# Vayu.net
KiCad netlist of a schematic drawn in EAGLE
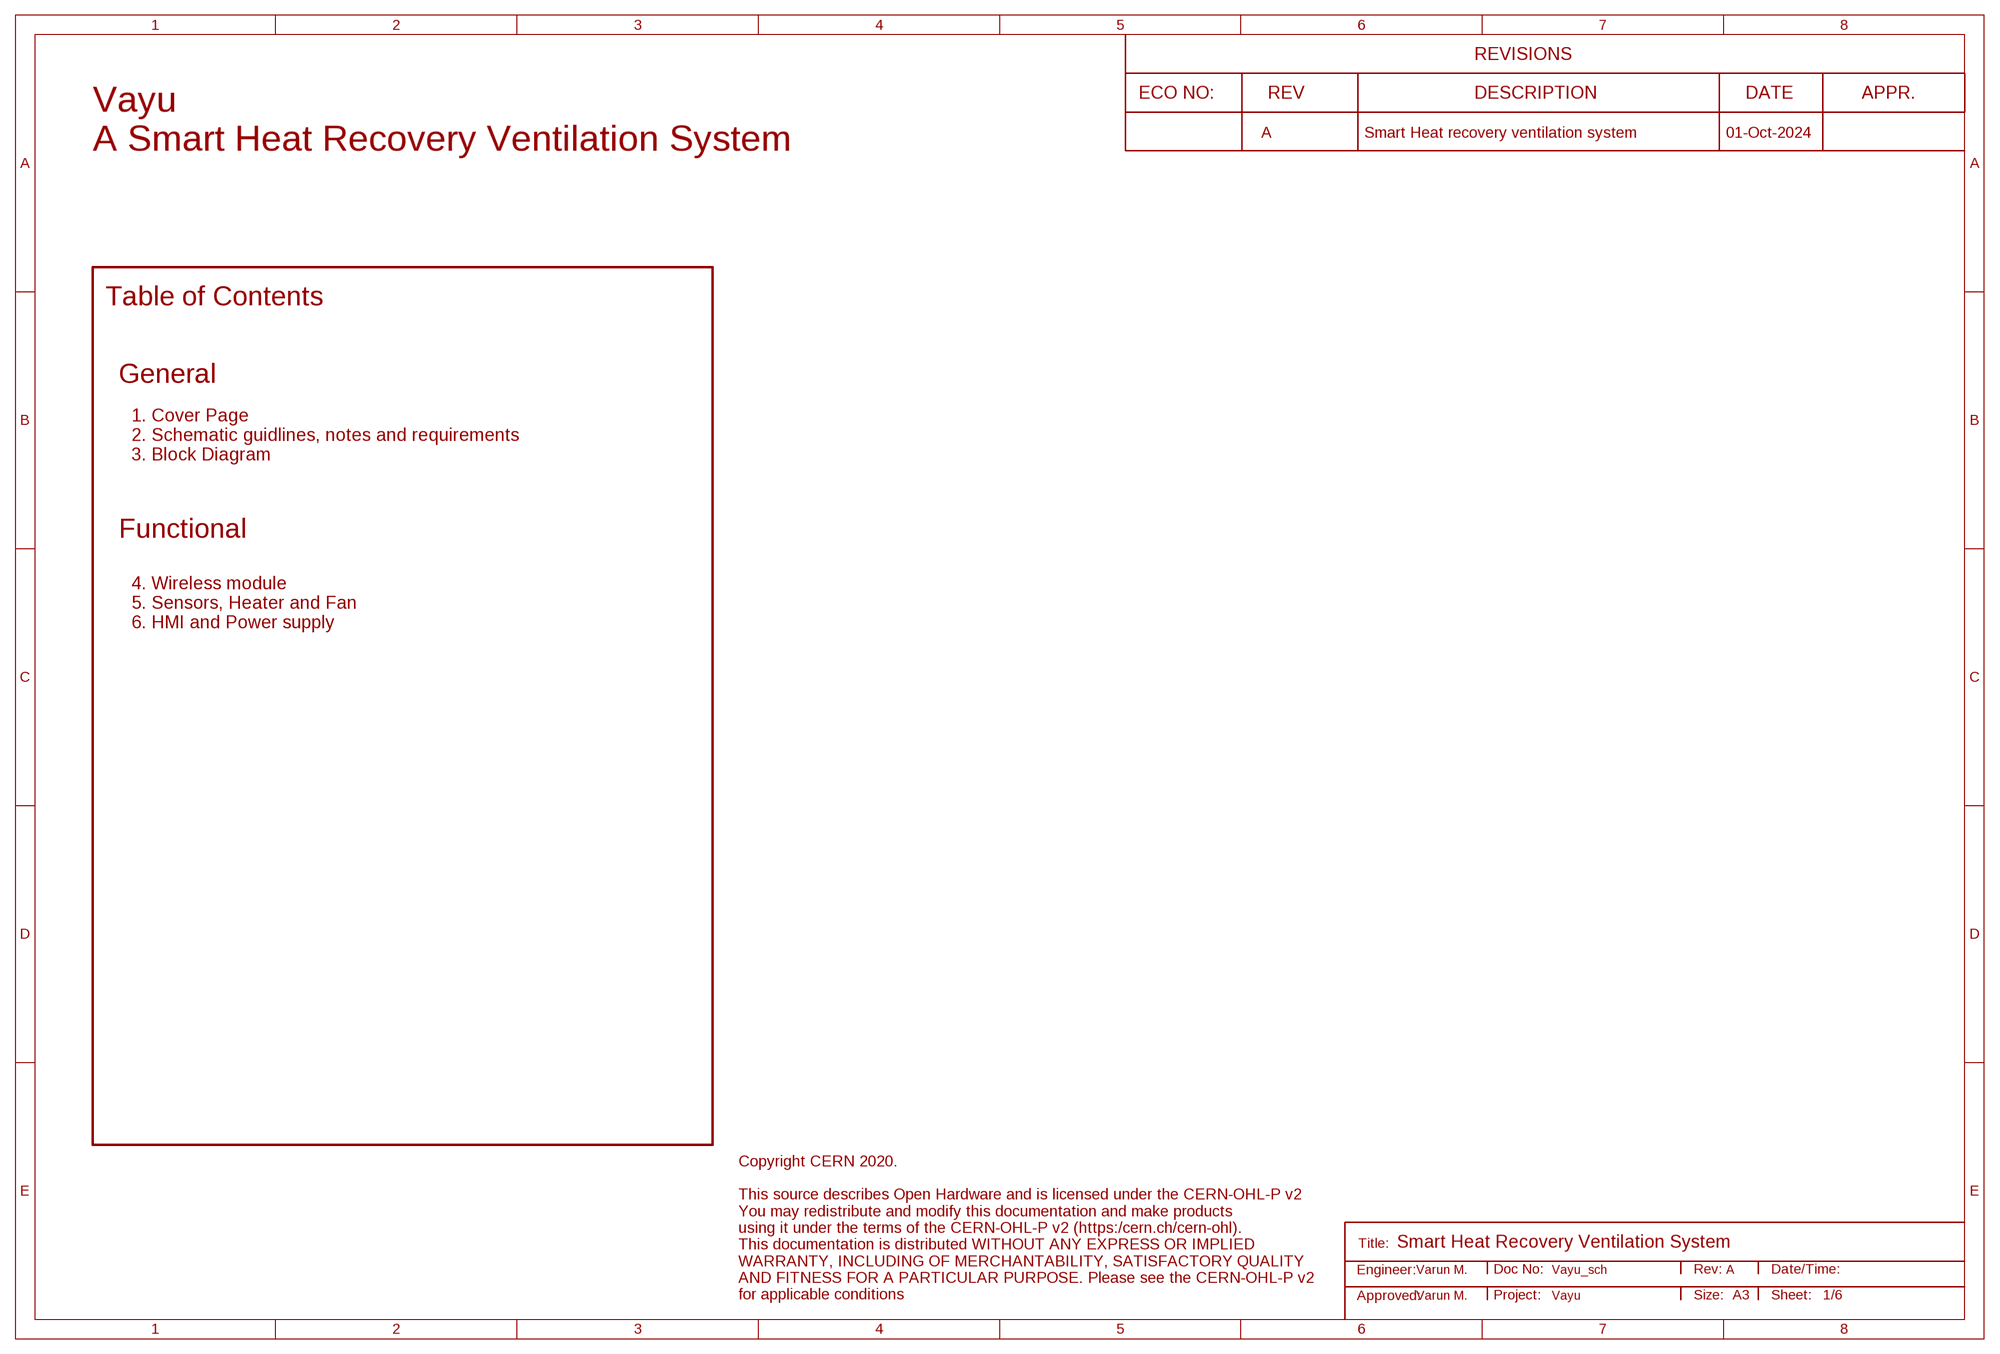
[diagram p0: schematic, sheet 1]
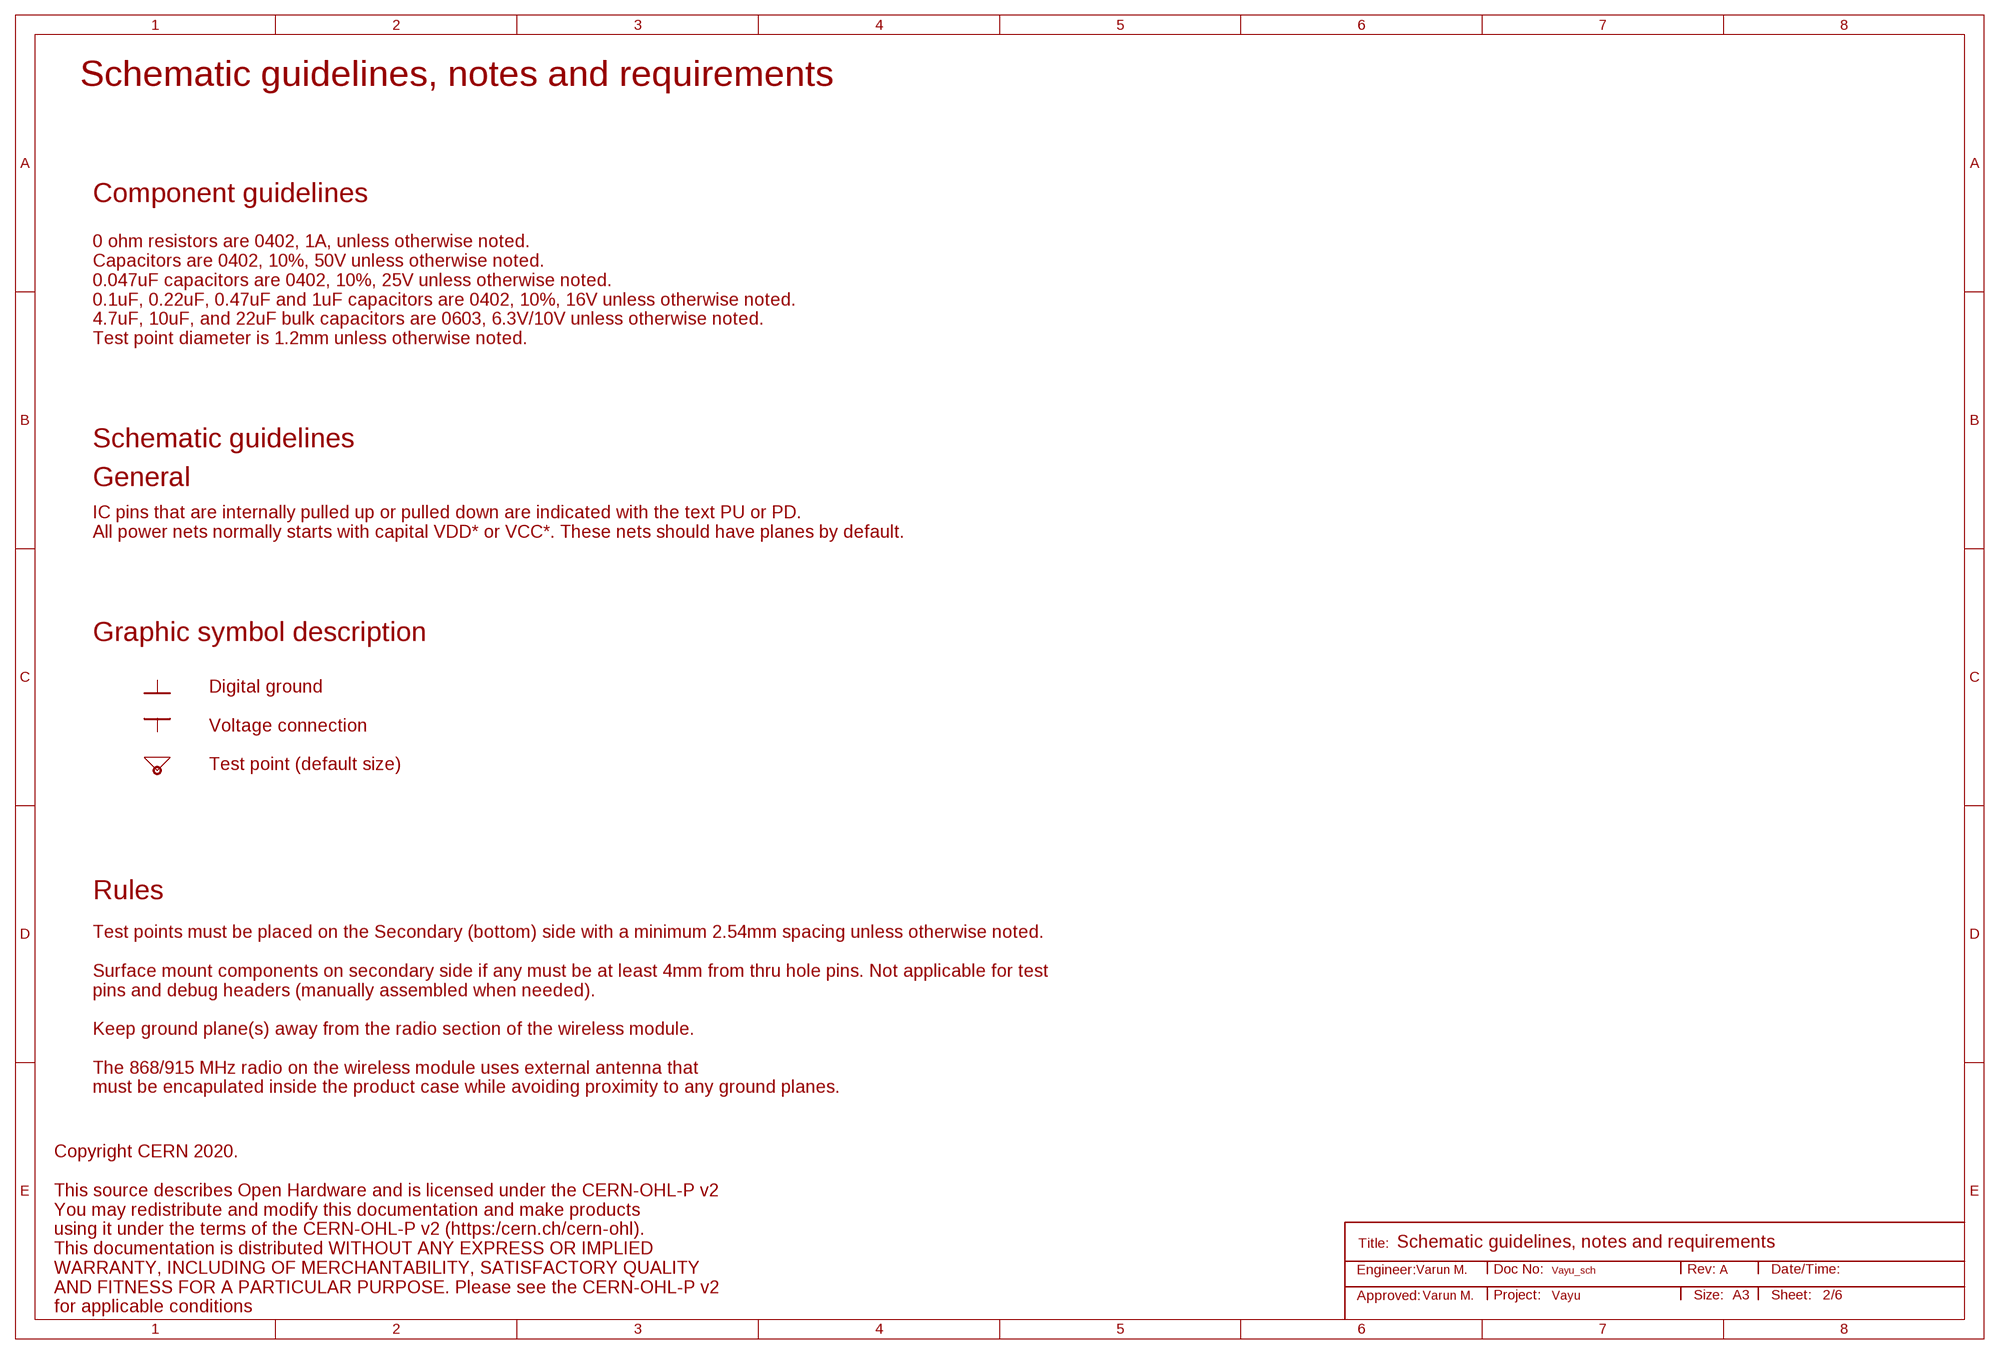
[diagram p1: schematic, sheet 2]
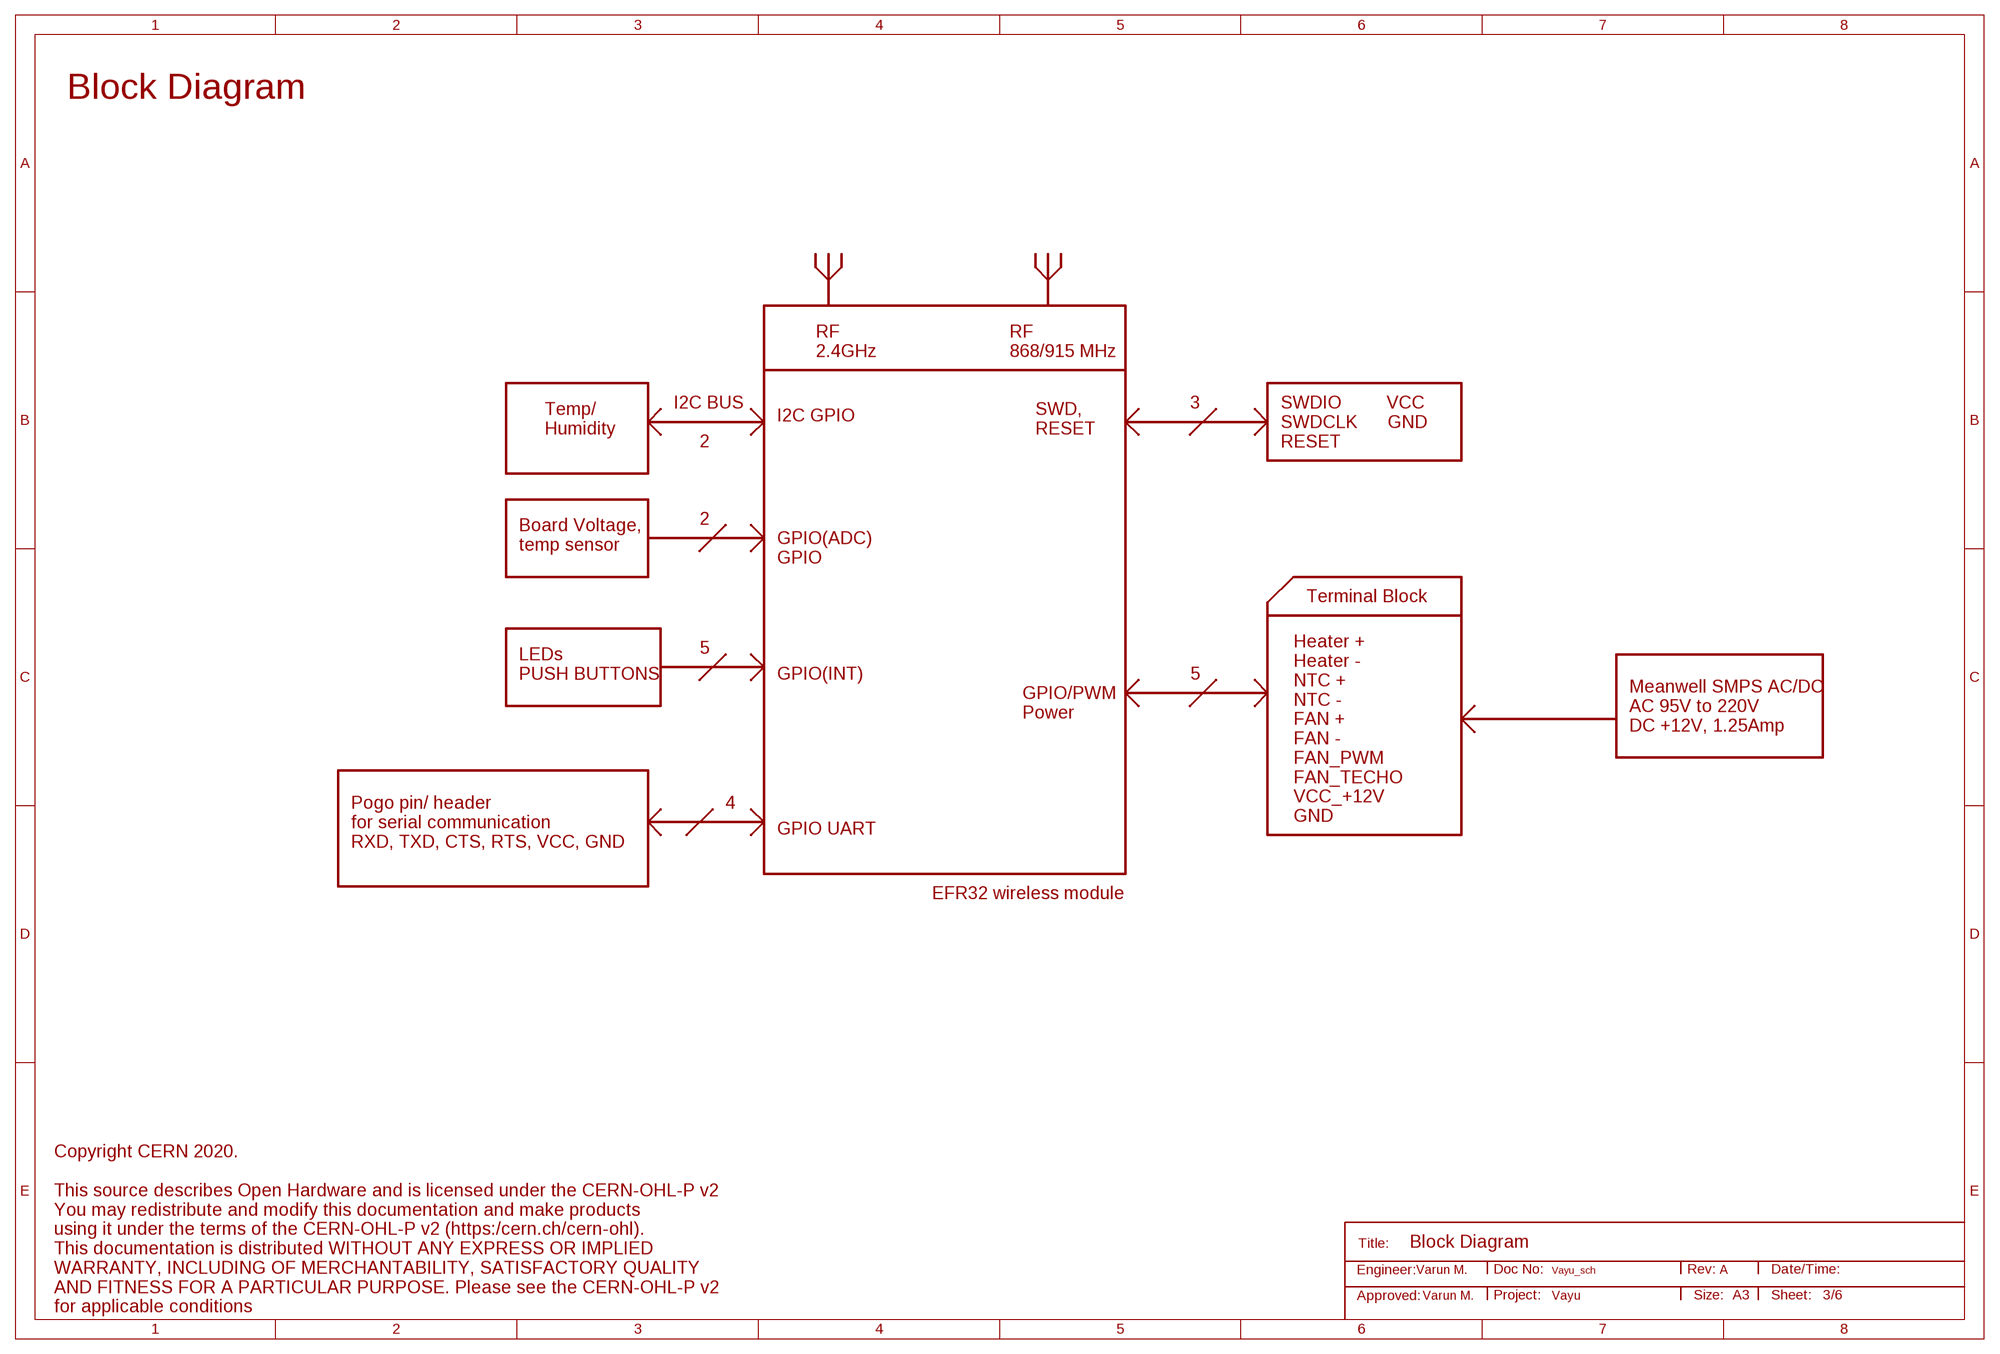
[diagram p2: schematic, sheet 3]
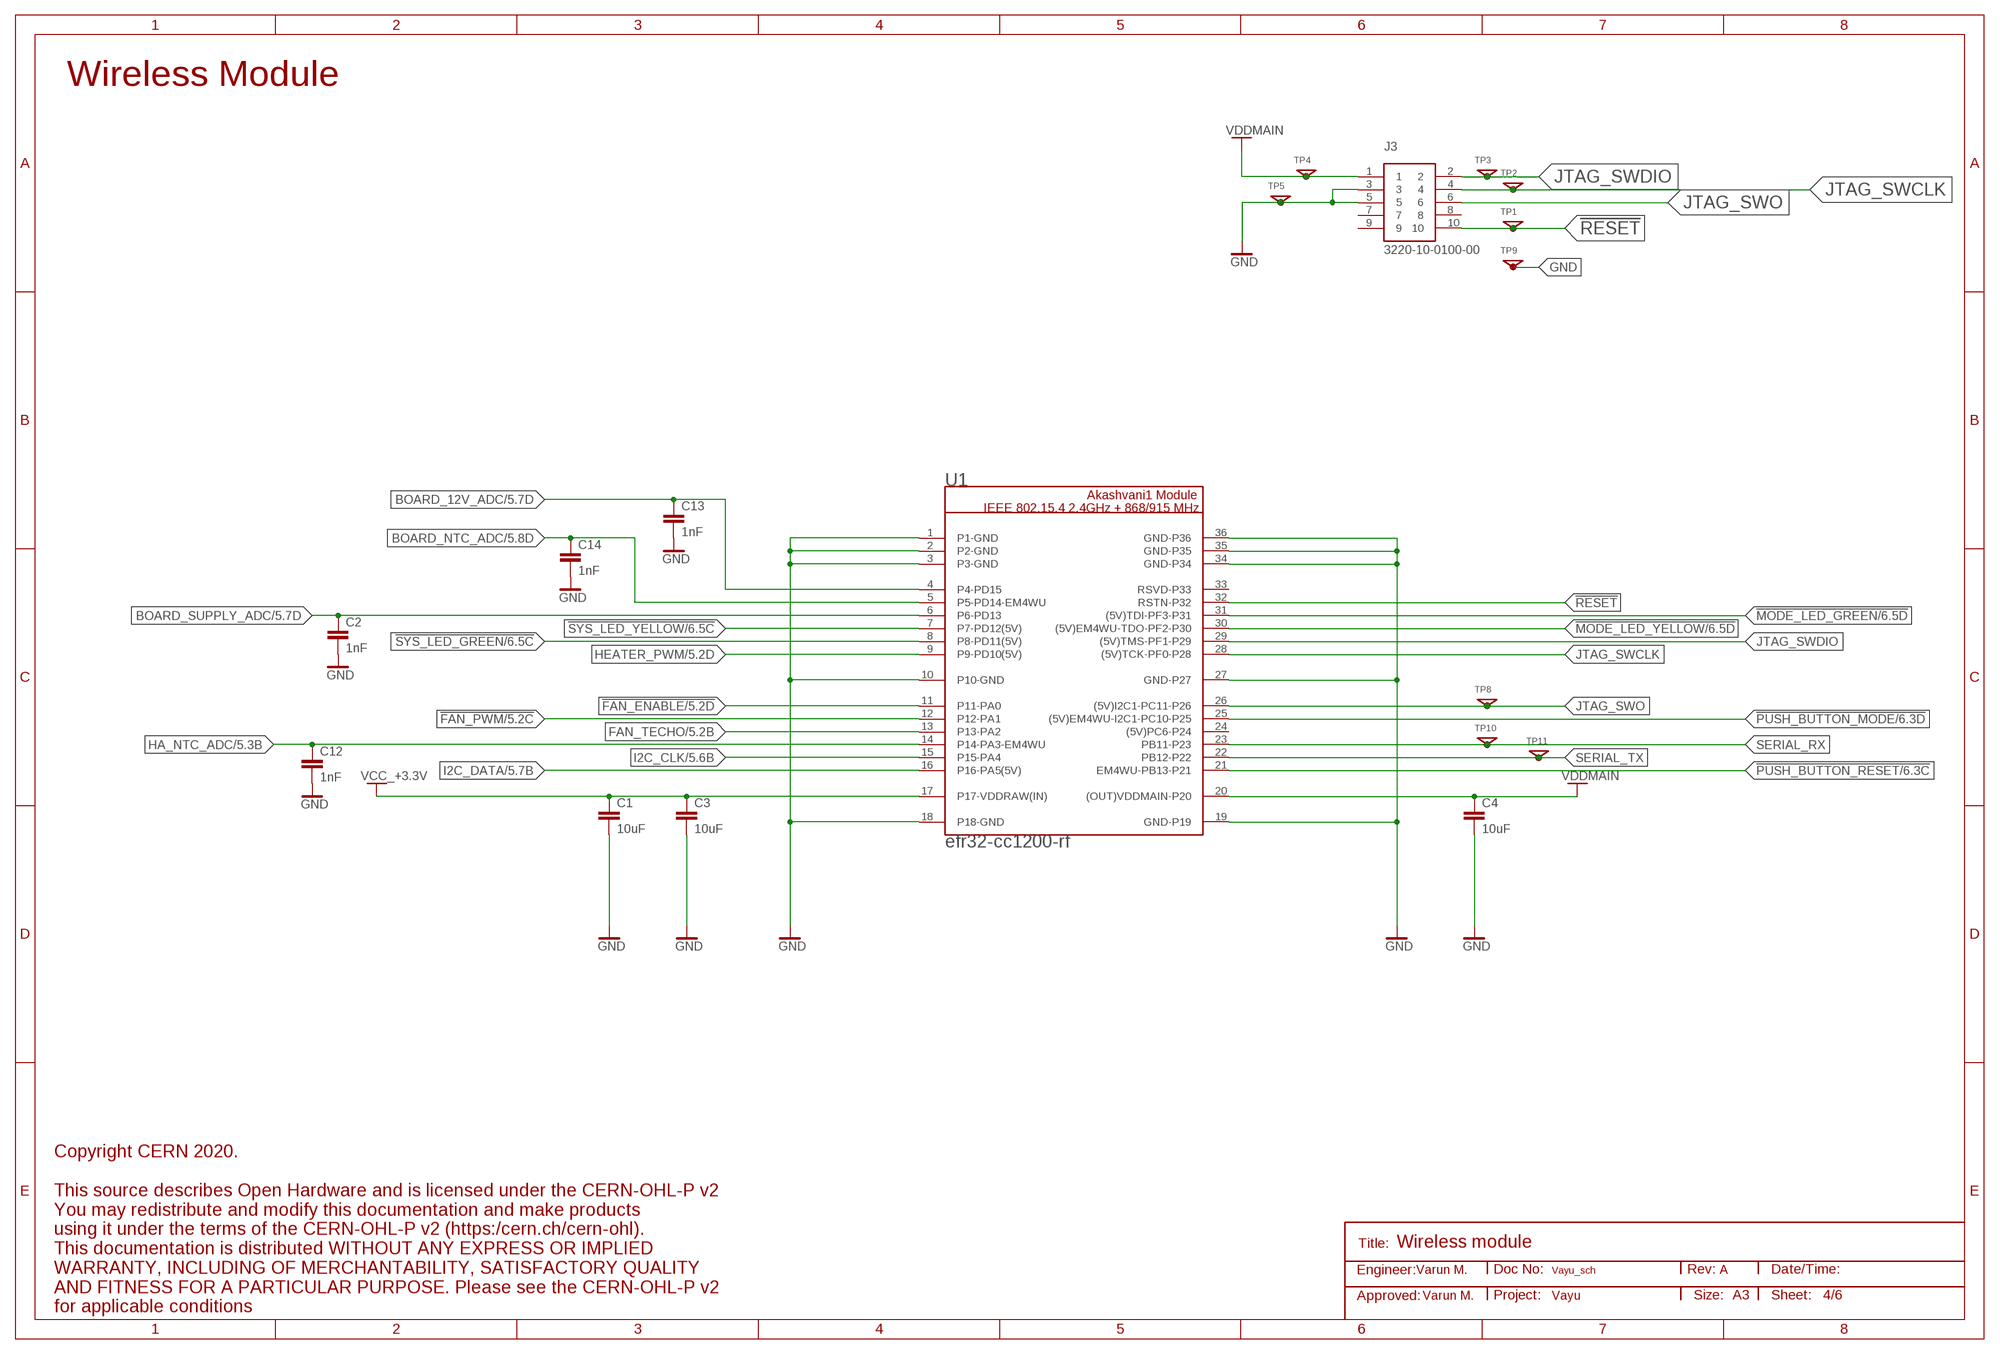
[diagram p3: schematic, sheet 4]
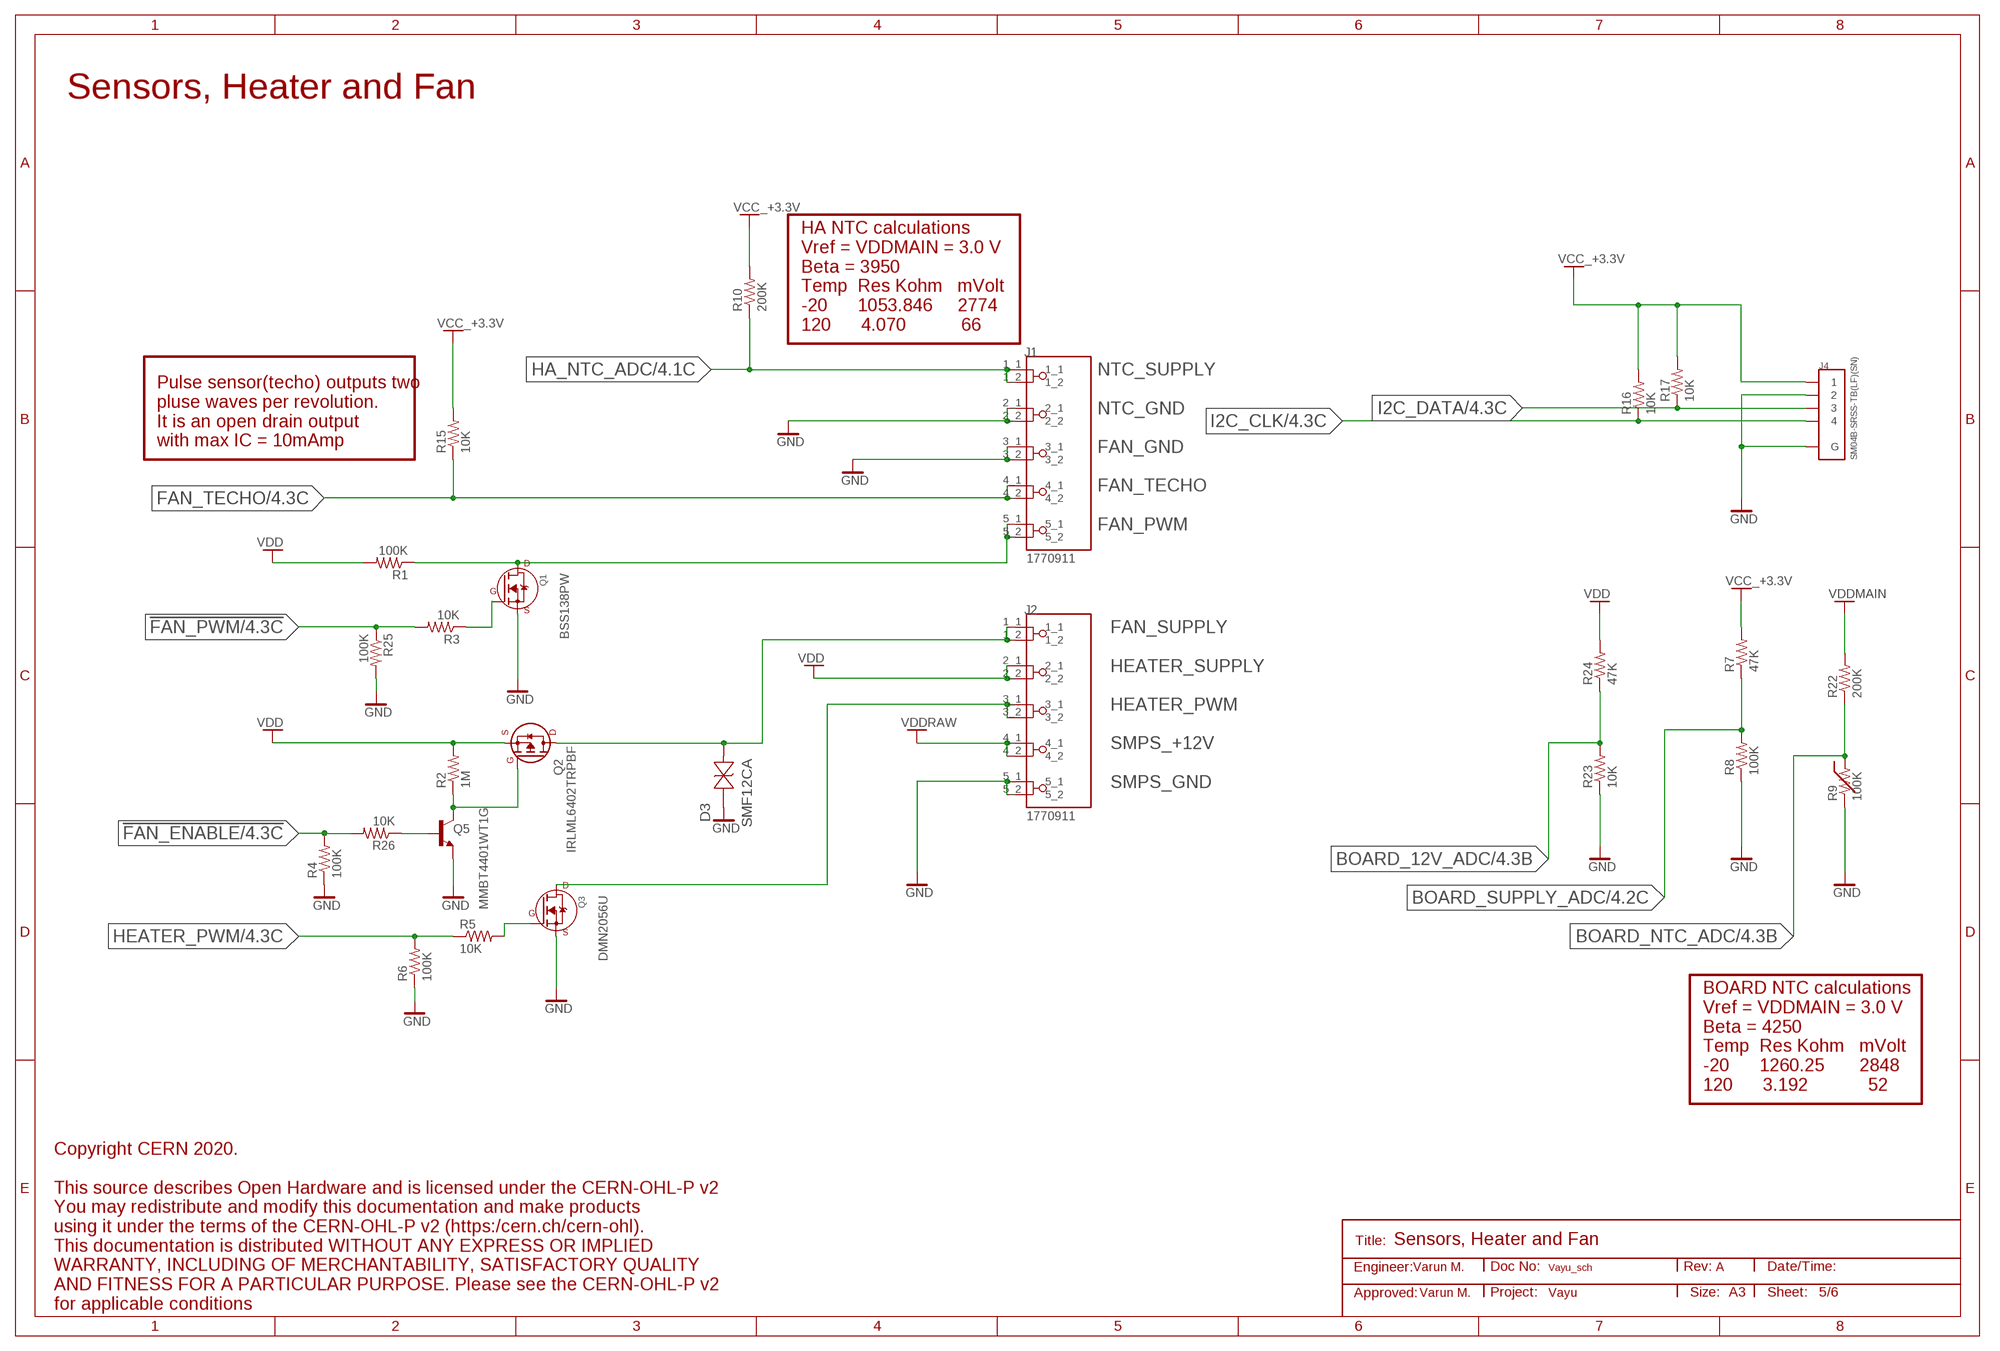
[diagram p4: schematic, sheet 5]
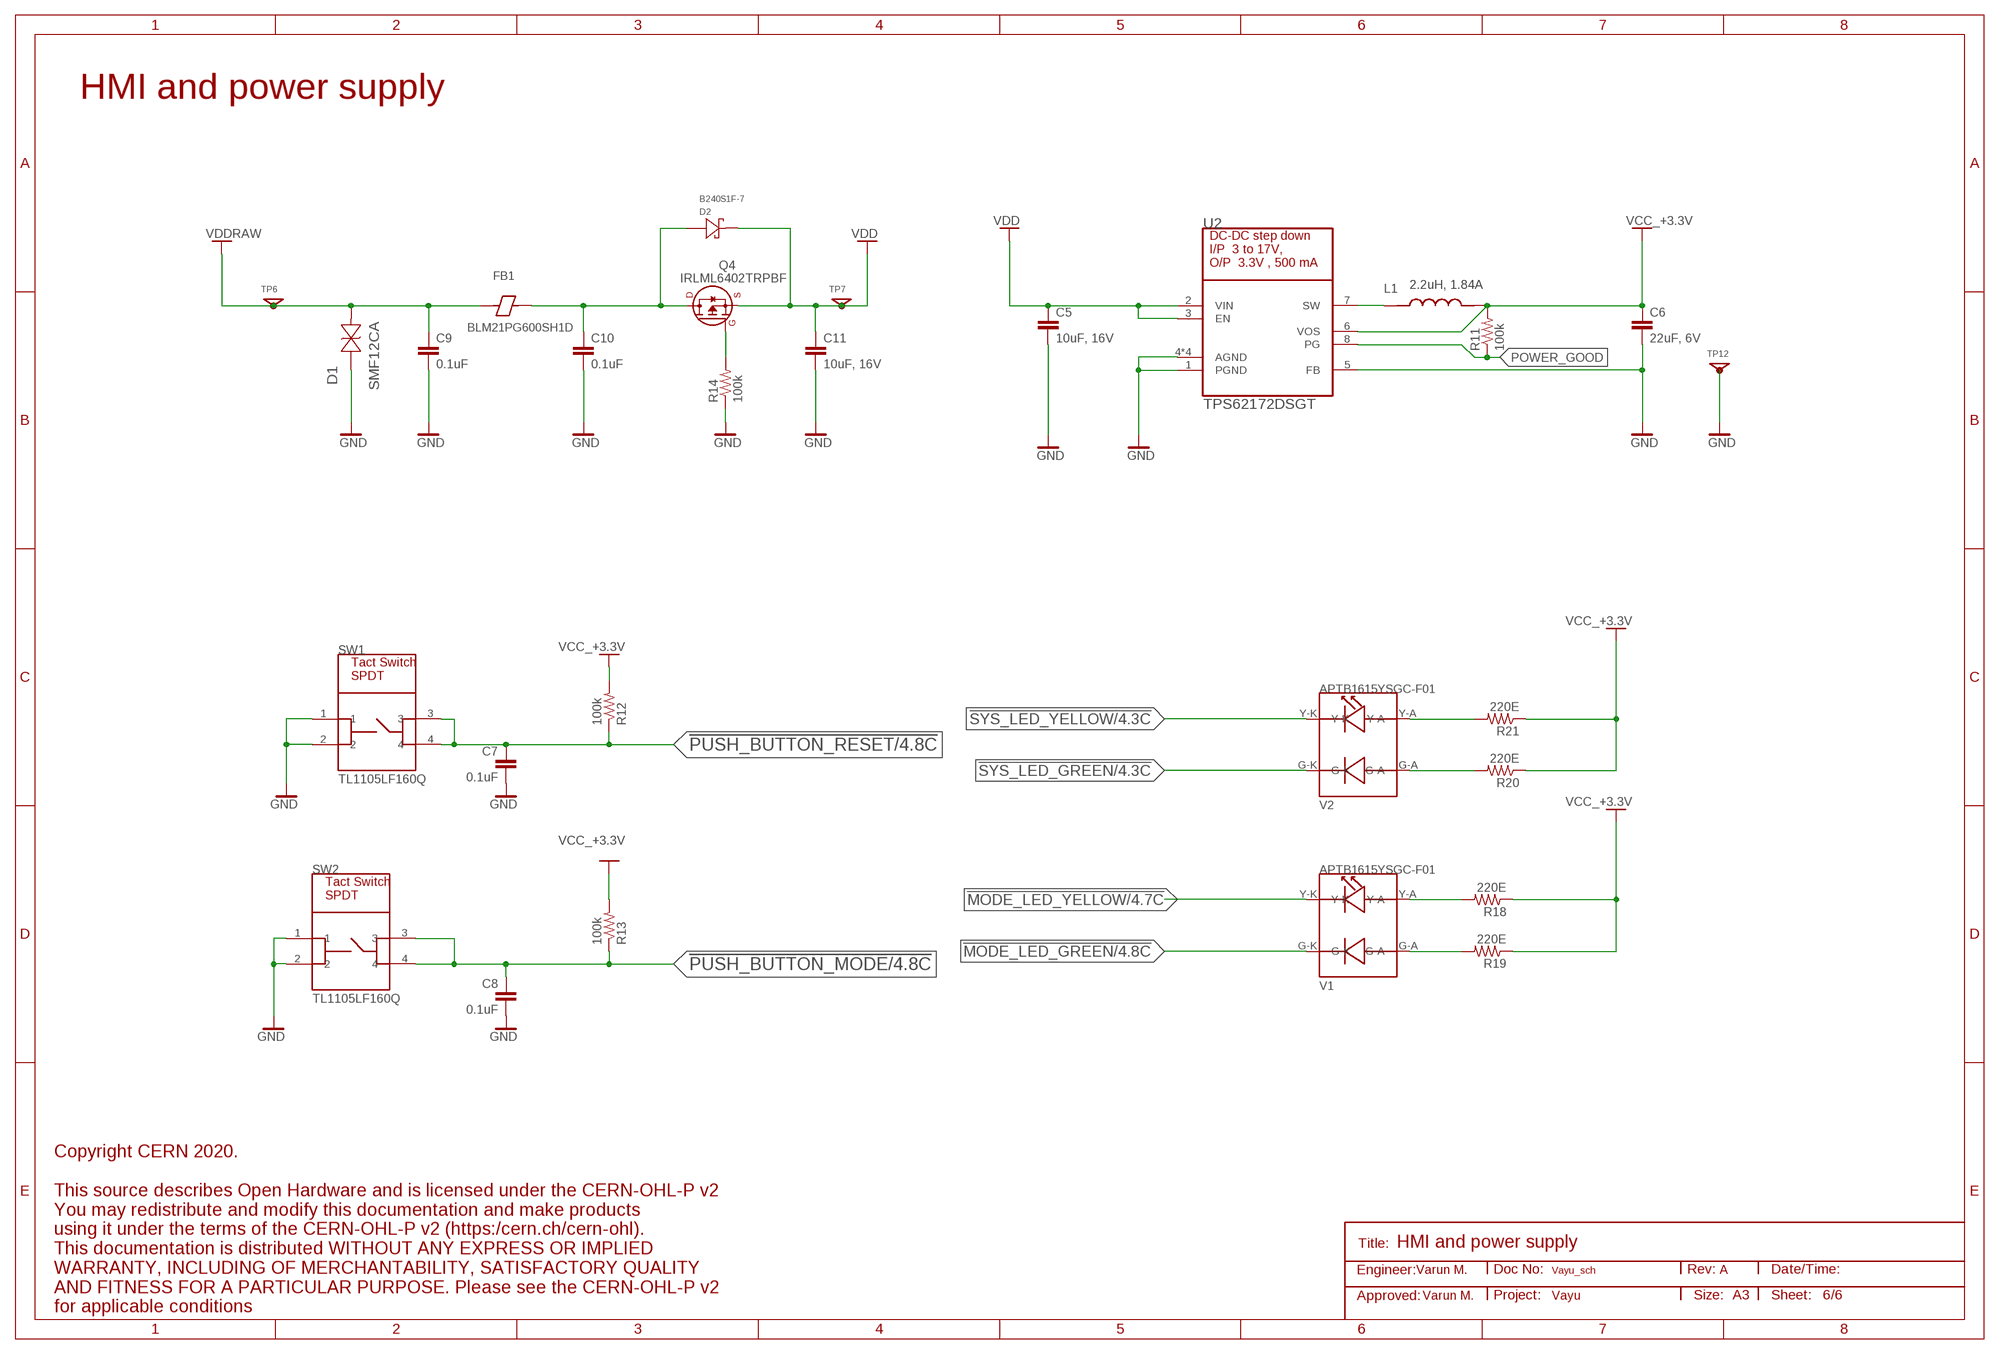
[diagram p5: schematic, sheet 6]

(export (version "E")
  (design (tool "Eeschema 10.0.6"))
  (components
    (comp (ref "D3")
      (value "SMF12CA")
      (footprint "eagle-import:SOD-123F-BI")
      (libsource (lib "eagle-import") (part "SMF12CA"))
    )
    (comp (ref "J1")
      (value "1770911")
      (footprint "eagle-import:PHOENIX_1770911")
      (fields (field (name "MANUFACTURER") "PHOENIX"))
      (libsource (lib "eagle-import") (part "1770911"))
    )
    (comp (ref "J2")
      (value "1770911")
      (footprint "eagle-import:PHOENIX_1770911")
      (fields (field (name "MANUFACTURER") "PHOENIX"))
      (libsource (lib "eagle-import") (part "1770911"))
    )
    (comp (ref "J4")
      (value "SM04B-SRSS-TB(LF)(SN)")
      (footprint "eagle-import:JST_SM04B-SRSS-TB(LF)(SN)")
      (fields (field (name "DIGI-KEY_PART_NUMBER") "455-1804-1-ND") (field (name "MF") "JST Sales"))
      (libsource (lib "eagle-import") (part "SM04B-SRSS-TB(LF)(SN)"))
    )
    (comp (ref "Q1")
      (value "BSS138PW")
      (footprint "eagle-import:SC-70_SOT323")
      (libsource (lib "eagle-import") (part "BSS138PW"))
    )
    (comp (ref "Q2")
      (value "IRLML6402TRPBF")
      (footprint "eagle-import:SOT23-3")
      (libsource (lib "eagle-import") (part "IRLML6402TRPBF"))
    )
    (comp (ref "Q3")
      (value "DMN2056U")
      (footprint "eagle-import:SOT23-3")
      (libsource (lib "eagle-import") (part "DMN2056U"))
    )
    (comp (ref "Q5")
      (value "MMBT4401WT1G")
      (footprint "eagle-import:SOT323-BEC")
      (libsource (lib "eagle-import") (part "MMBT4401WT1G"))
    )
    (comp (ref "R1")
      (value "100K")
      (footprint "eagle-import:R0402")
      (libsource (lib "eagle-import") (part "R-US_R0402"))
    )
    (comp (ref "R2")
      (value "1M")
      (footprint "eagle-import:R0402")
      (libsource (lib "eagle-import") (part "R-US_R0402"))
    )
    (comp (ref "R3")
      (value "10K")
      (footprint "eagle-import:R0402")
      (libsource (lib "eagle-import") (part "R-US_R0402"))
    )
    (comp (ref "R4")
      (value "100K")
      (footprint "eagle-import:R0402")
      (libsource (lib "eagle-import") (part "R-US_R0402"))
    )
    (comp (ref "R5")
      (value "10K")
      (footprint "eagle-import:R0402")
      (libsource (lib "eagle-import") (part "R-US_R0402"))
    )
    (comp (ref "R6")
      (value "100K")
      (footprint "eagle-import:R0402")
      (libsource (lib "eagle-import") (part "R-US_R0402"))
    )
    (comp (ref "R7")
      (value "47K")
      (footprint "eagle-import:R0402")
      (libsource (lib "eagle-import") (part "R-US_R0402"))
    )
    (comp (ref "R8")
      (value "100K")
      (footprint "eagle-import:R0402")
      (libsource (lib "eagle-import") (part "R-US_R0402"))
    )
    (comp (ref "R9")
      (value "100K")
      (footprint "eagle-import:R0402")
      (libsource (lib "eagle-import") (part "R-NTCR0402"))
    )
    (comp (ref "R10")
      (value "200K")
      (footprint "eagle-import:R0402")
      (libsource (lib "eagle-import") (part "R-US_R0402"))
    )
    (comp (ref "R15")
      (value "10K")
      (footprint "eagle-import:R0402")
      (libsource (lib "eagle-import") (part "R-US_R0402"))
    )
    (comp (ref "R16")
      (value "10K")
      (footprint "eagle-import:R0402")
      (libsource (lib "eagle-import") (part "R-US_R0402"))
    )
    (comp (ref "R17")
      (value "10K")
      (footprint "eagle-import:R0402")
      (libsource (lib "eagle-import") (part "R-US_R0402"))
    )
    (comp (ref "R22")
      (value "200K")
      (footprint "eagle-import:R0402")
      (libsource (lib "eagle-import") (part "R-US_R0402"))
    )
    (comp (ref "R23")
      (value "10K")
      (footprint "eagle-import:R0402")
      (libsource (lib "eagle-import") (part "R-US_R0402"))
    )
    (comp (ref "R24")
      (value "47K")
      (footprint "eagle-import:R0402")
      (libsource (lib "eagle-import") (part "R-US_R0402"))
    )
    (comp (ref "R25")
      (value "100K")
      (footprint "eagle-import:R0402")
      (libsource (lib "eagle-import") (part "R-US_R0402"))
    )
    (comp (ref "R26")
      (value "10K")
      (footprint "eagle-import:R0402")
      (libsource (lib "eagle-import") (part "R-US_R0402"))
    )
    (comp (ref "C5")
      (value "10uF, 16V")
      (footprint "eagle-import:C0805")
      (libsource (lib "eagle-import") (part "C-EUC0805"))
    )
    (comp (ref "C6")
      (value "22uF, 6V")
      (footprint "eagle-import:C0603")
      (libsource (lib "eagle-import") (part "C-EUC0603"))
    )
    (comp (ref "C7")
      (value "0.1uF")
      (footprint "eagle-import:CAPC1005X55N")
      (libsource (lib "eagle-import") (part "C-EUC0402S"))
    )
    (comp (ref "C8")
      (value "0.1uF")
      (footprint "eagle-import:CAPC1005X55N")
      (libsource (lib "eagle-import") (part "C-EUC0402S"))
    )
    (comp (ref "C9")
      (value "0.1uF")
      (footprint "eagle-import:CAPC1005X55N")
      (libsource (lib "eagle-import") (part "C-EUC0402S"))
    )
    (comp (ref "C10")
      (value "0.1uF")
      (footprint "eagle-import:CAPC1005X55N")
      (libsource (lib "eagle-import") (part "C-EUC0402S"))
    )
    (comp (ref "C11")
      (value "10uF, 16V")
      (footprint "eagle-import:C0805")
      (libsource (lib "eagle-import") (part "C-EUC0805"))
    )
    (comp (ref "D1")
      (value "SMF12CA")
      (footprint "eagle-import:SOD-123F-BI")
      (libsource (lib "eagle-import") (part "SMF12CA"))
    )
    (comp (ref "D2")
      (value "B240S1F-7")
      (footprint "eagle-import:SOD-123F")
      (libsource (lib "eagle-import") (part "MBR1020VL"))
    )
    (comp (ref "FB1")
      (value "BLM21PG600SH1D")
      (footprint "eagle-import:BEADC2012X105N")
      (fields (field (name "DIGI-KEY_PART_NUMBER") "490-7824-1-ND") (field (name "MF") "Murata Electronics"))
      (libsource (lib "eagle-import") (part "BLM21PG600SH1D"))
    )
    (comp (ref "L1")
      (value "2.2uH, 1.84A")
      (footprint "eagle-import:IND_VLS201612HBX-2R2M-1")
      (fields (field (name "MANUFACTURER") "TDK"))
      (libsource (lib "eagle-import") (part "VLS201612HBX-2R2M-1"))
    )
    (comp (ref "Q4")
      (value "IRLML6402TRPBF")
      (footprint "eagle-import:SOT23-3")
      (libsource (lib "eagle-import") (part "IRLML6402TRPBF"))
    )
    (comp (ref "R11")
      (value "100k")
      (footprint "eagle-import:R0402")
      (libsource (lib "eagle-import") (part "R-US_R0402"))
    )
    (comp (ref "R12")
      (value "100k")
      (footprint "eagle-import:R0402")
      (libsource (lib "eagle-import") (part "R-US_R0402"))
    )
    (comp (ref "R13")
      (value "100k")
      (footprint "eagle-import:R0402")
      (libsource (lib "eagle-import") (part "R-US_R0402"))
    )
    (comp (ref "R14")
      (value "100k")
      (footprint "eagle-import:R0402")
      (libsource (lib "eagle-import") (part "R-US_R0402"))
    )
    (comp (ref "R18")
      (value "220E")
      (footprint "eagle-import:R0402")
      (libsource (lib "eagle-import") (part "R-US_R0402"))
    )
    (comp (ref "R19")
      (value "220E")
      (footprint "eagle-import:R0402")
      (libsource (lib "eagle-import") (part "R-US_R0402"))
    )
    (comp (ref "R20")
      (value "220E")
      (footprint "eagle-import:R0402")
      (libsource (lib "eagle-import") (part "R-US_R0402"))
    )
    (comp (ref "R21")
      (value "220E")
      (footprint "eagle-import:R0402")
      (libsource (lib "eagle-import") (part "R-US_R0402"))
    )
    (comp (ref "SW1")
      (value "TL1105LF160Q")
      (footprint "eagle-import:TACT_TH_6X6X17MM")
      (libsource (lib "eagle-import") (part "TL1105LF160Q"))
    )
    (comp (ref "SW2")
      (value "TL1105LF160Q")
      (footprint "eagle-import:TACT_TH_6X6X17MM")
      (libsource (lib "eagle-import") (part "TL1105LF160Q"))
    )
    (comp (ref "TP6")
      (value "TP_1.2")
      (footprint "eagle-import:TP_1.2")
      (libsource (lib "eagle-import") (part "TP_1.2"))
    )
    (comp (ref "TP7")
      (value "TP_1.2")
      (footprint "eagle-import:TP_1.2")
      (libsource (lib "eagle-import") (part "TP_1.2"))
    )
    (comp (ref "TP12")
      (value "TP_1.2")
      (footprint "eagle-import:TP_1.2")
      (libsource (lib "eagle-import") (part "TP_1.2"))
    )
    (comp (ref "U2")
      (value "TPS62172DSGT")
      (footprint "eagle-import:SON50P200X200X80-9N")
      (libsource (lib "eagle-import") (part "TPS62172DSGT"))
    )
    (comp (ref "V1")
      (value "APTB1615YSGC-F01")
      (footprint "eagle-import:LED-0606")
      (libsource (lib "eagle-import") (part "APTB1615YSGC-F01"))
    )
    (comp (ref "V2")
      (value "APTB1615YSGC-F01")
      (footprint "eagle-import:LED-0606")
      (libsource (lib "eagle-import") (part "APTB1615YSGC-F01"))
    )
    (comp (ref "C1")
      (value "10uF")
      (footprint "eagle-import:C0603")
      (libsource (lib "eagle-import") (part "C-EUC0603"))
    )
    (comp (ref "C2")
      (value "1nF")
      (footprint "eagle-import:CAPC1005X55N")
      (libsource (lib "eagle-import") (part "C-EUC0402S"))
    )
    (comp (ref "C3")
      (value "10uF")
      (footprint "eagle-import:C0603")
      (libsource (lib "eagle-import") (part "C-EUC0603"))
    )
    (comp (ref "C4")
      (value "10uF")
      (footprint "eagle-import:C0603")
      (libsource (lib "eagle-import") (part "C-EUC0603"))
    )
    (comp (ref "C12")
      (value "1nF")
      (footprint "eagle-import:CAPC1005X55N")
      (libsource (lib "eagle-import") (part "C-EUC0402S"))
    )
    (comp (ref "C13")
      (value "1nF")
      (footprint "eagle-import:CAPC1005X55N")
      (libsource (lib "eagle-import") (part "C-EUC0402S"))
    )
    (comp (ref "C14")
      (value "1nF")
      (footprint "eagle-import:CAPC1005X55N")
      (libsource (lib "eagle-import") (part "C-EUC0402S"))
    )
    (comp (ref "J3")
      (value "3220-10-0100-00")
      (footprint "eagle-import:PIN2X5_1.27MM")
      (libsource (lib "eagle-import") (part "3220-10-0100-00"))
    )
    (comp (ref "TP1")
      (value "TP_1.2")
      (footprint "eagle-import:TP_1.2")
      (libsource (lib "eagle-import") (part "TP_1.2"))
    )
    (comp (ref "TP2")
      (value "TP_1.2")
      (footprint "eagle-import:TP_1.2")
      (libsource (lib "eagle-import") (part "TP_1.2"))
    )
    (comp (ref "TP3")
      (value "TP_1.2")
      (footprint "eagle-import:TP_1.2")
      (libsource (lib "eagle-import") (part "TP_1.2"))
    )
    (comp (ref "TP4")
      (value "TP_1.2")
      (footprint "eagle-import:TP_1.2")
      (libsource (lib "eagle-import") (part "TP_1.2"))
    )
    (comp (ref "TP5")
      (value "TP_1.2")
      (footprint "eagle-import:TP_1.2")
      (libsource (lib "eagle-import") (part "TP_1.2"))
    )
    (comp (ref "TP8")
      (value "TP_1.2")
      (footprint "eagle-import:TP_1.2")
      (libsource (lib "eagle-import") (part "TP_1.2"))
    )
    (comp (ref "TP9")
      (value "TP_1.2")
      (footprint "eagle-import:TP_1.2")
      (libsource (lib "eagle-import") (part "TP_1.2"))
    )
    (comp (ref "TP10")
      (value "TP_1.2")
      (footprint "eagle-import:TP_1.2")
      (libsource (lib "eagle-import") (part "TP_1.2"))
    )
    (comp (ref "TP11")
      (value "TP_1.2")
      (footprint "eagle-import:TP_1.2")
      (libsource (lib "eagle-import") (part "TP_1.2"))
    )
    (comp (ref "U1")
      (value "efr32-cc1200-rf")
      (footprint "eagle-import:AKASHVANI1")
      (libsource (lib "eagle-import") (part "AKASHVANI1"))
    )
  )
  (nets
    (net (code "1") (name "BOARD_12V_ADC") (class "Default")
      (node (ref "C13") (pin "1") (pinfunction "1_1") (pintype "passive"))
      (node (ref "R23") (pin "2") (pinfunction "2_2") (pintype "passive"))
      (node (ref "R24") (pin "1") (pinfunction "1_1") (pintype "passive"))
      (node (ref "U1") (pin "4") (pinfunction "P4-PD15_4") (pintype "bidirectional"))
    )
    (net (code "2") (name "BOARD_NTC_ADC") (class "Default")
      (node (ref "C14") (pin "1") (pinfunction "1_1") (pintype "passive"))
      (node (ref "R22") (pin "1") (pinfunction "1_1") (pintype "passive"))
      (node (ref "R9") (pin "2") (pinfunction "2_2") (pintype "passive"))
      (node (ref "U1") (pin "5") (pinfunction "P5-PD14-EM4WU_5") (pintype "bidirectional"))
    )
    (net (code "3") (name "BOARD_SUPPLY_ADC") (class "Default")
      (node (ref "C2") (pin "1") (pinfunction "1_1") (pintype "passive"))
      (node (ref "R7") (pin "1") (pinfunction "1_1") (pintype "passive"))
      (node (ref "R8") (pin "2") (pinfunction "2_2") (pintype "passive"))
      (node (ref "U1") (pin "6") (pinfunction "P6-PD13_6") (pintype "bidirectional"))
    )
    (net (code "4") (name "FAN_TECHO") (class "Default")
      (node (ref "J1") (pin "4_1") (pinfunction "4_1_4_1") (pintype "passive"))
      (node (ref "J1") (pin "4_2") (pinfunction "4_2_4_2") (pintype "passive"))
      (node (ref "R15") (pin "1") (pinfunction "1_1") (pintype "passive"))
      (node (ref "U1") (pin "13") (pinfunction "P13-PA2_13") (pintype "bidirectional"))
    )
    (net (code "5") (name "GND") (class "Default")
      (node (ref "C1") (pin "2") (pinfunction "2_2") (pintype "passive"))
      (node (ref "C10") (pin "2") (pinfunction "2_2") (pintype "passive"))
      (node (ref "C11") (pin "2") (pinfunction "2_2") (pintype "passive"))
      (node (ref "C12") (pin "2") (pinfunction "2_2") (pintype "passive"))
      (node (ref "C13") (pin "2") (pinfunction "2_2") (pintype "passive"))
      (node (ref "C14") (pin "2") (pinfunction "2_2") (pintype "passive"))
      (node (ref "C2") (pin "2") (pinfunction "2_2") (pintype "passive"))
      (node (ref "C3") (pin "2") (pinfunction "2_2") (pintype "passive"))
      (node (ref "C4") (pin "2") (pinfunction "2_2") (pintype "passive"))
      (node (ref "C5") (pin "2") (pinfunction "2_2") (pintype "passive"))
      (node (ref "C6") (pin "2") (pinfunction "2_2") (pintype "passive"))
      (node (ref "C7") (pin "2") (pinfunction "2_2") (pintype "passive"))
      (node (ref "C8") (pin "2") (pinfunction "2_2") (pintype "passive"))
      (node (ref "C9") (pin "2") (pinfunction "2_2") (pintype "passive"))
      (node (ref "D1") (pin "2") (pinfunction "12_2") (pintype "passive"))
      (node (ref "D3") (pin "2") (pinfunction "12_2") (pintype "passive"))
      (node (ref "J1") (pin "2_1") (pinfunction "2_1_2_1") (pintype "passive"))
      (node (ref "J1") (pin "2_2") (pinfunction "2_2_2_2") (pintype "passive"))
      (node (ref "J1") (pin "3_1") (pinfunction "3_1_3_1") (pintype "passive"))
      (node (ref "J1") (pin "3_2") (pinfunction "3_2_3_2") (pintype "passive"))
      (node (ref "J2") (pin "5_1") (pinfunction "5_1_5_1") (pintype "passive"))
      (node (ref "J2") (pin "5_2") (pinfunction "5_2_5_2") (pintype "passive"))
      (node (ref "J3") (pin "3") (pinfunction "3_3") (pintype "bidirectional"))
      (node (ref "J3") (pin "5") (pinfunction "5_5") (pintype "bidirectional"))
      (node (ref "J4") (pin "2") (pinfunction "2_2") (pintype "passive"))
      (node (ref "J4") (pin "S1") (pinfunction "G_S1") (pintype "passive"))
      (node (ref "J4") (pin "S2") (pinfunction "G_S2") (pintype "passive"))
      (node (ref "Q1") (pin "2") (pinfunction "S_2") (pintype "passive"))
      (node (ref "Q3") (pin "S") (pinfunction "S_S") (pintype "passive"))
      (node (ref "Q5") (pin "E") (pinfunction "E_E") (pintype "passive"))
      (node (ref "R14") (pin "1") (pinfunction "1_1") (pintype "passive"))
      (node (ref "R23") (pin "1") (pinfunction "1_1") (pintype "passive"))
      (node (ref "R25") (pin "2") (pinfunction "2_2") (pintype "passive"))
      (node (ref "R4") (pin "1") (pinfunction "1_1") (pintype "passive"))
      (node (ref "R6") (pin "1") (pinfunction "1_1") (pintype "passive"))
      (node (ref "R8") (pin "1") (pinfunction "1_1") (pintype "passive"))
      (node (ref "R9") (pin "1") (pinfunction "1_1") (pintype "passive"))
      (node (ref "SW1") (pin "1") (pinfunction "1_1") (pintype "bidirectional"))
      (node (ref "SW1") (pin "2") (pinfunction "2_2") (pintype "bidirectional"))
      (node (ref "SW2") (pin "1") (pinfunction "1_1") (pintype "bidirectional"))
      (node (ref "SW2") (pin "2") (pinfunction "2_2") (pintype "bidirectional"))
      (node (ref "TP12") (pin "1") (pinfunction "TP_1") (pintype "bidirectional"))
      (node (ref "TP5") (pin "1") (pinfunction "TP_1") (pintype "bidirectional"))
      (node (ref "TP9") (pin "1") (pinfunction "TP_1") (pintype "bidirectional"))
      (node (ref "U1") (pin "1") (pinfunction "P1-GND_1") (pintype "bidirectional"))
      (node (ref "U1") (pin "10") (pinfunction "P10-GND_10") (pintype "bidirectional"))
      (node (ref "U1") (pin "18") (pinfunction "P18-GND_18") (pintype "bidirectional"))
      (node (ref "U1") (pin "19") (pinfunction "GND-P19_19") (pintype "bidirectional"))
      (node (ref "U1") (pin "2") (pinfunction "P2-GND_2") (pintype "bidirectional"))
      (node (ref "U1") (pin "27") (pinfunction "GND-P27_27") (pintype "bidirectional"))
      (node (ref "U1") (pin "3") (pinfunction "P3-GND_3") (pintype "bidirectional"))
      (node (ref "U1") (pin "34") (pinfunction "GND-P34_34") (pintype "bidirectional"))
      (node (ref "U1") (pin "35") (pinfunction "GND-P35_35") (pintype "bidirectional"))
      (node (ref "U1") (pin "36") (pinfunction "GND-P36_36") (pintype "bidirectional"))
      (node (ref "U2") (pin "1") (pinfunction "PGND_1") (pintype "power_in"))
      (node (ref "U2") (pin "4") (pinfunction "AGND_4") (pintype "power_in"))
      (node (ref "U2") (pin "5") (pinfunction "FB_5") (pintype "bidirectional"))
      (node (ref "U2") (pin "9") (pinfunction "AGND_9") (pintype "power_in"))
      (node (ref "U2") (pin "9_1") (pinfunction "AGND_9_1") (pintype "power_in"))
      (node (ref "U2") (pin "9_2") (pinfunction "AGND_9_2") (pintype "power_in"))
    )
    (net (code "6") (name "HA_NTC_ADC") (class "Default")
      (node (ref "C12") (pin "1") (pinfunction "1_1") (pintype "passive"))
      (node (ref "J1") (pin "1_1") (pinfunction "1_1_1_1") (pintype "passive"))
      (node (ref "J1") (pin "1_2") (pinfunction "1_2_1_2") (pintype "passive"))
      (node (ref "R10") (pin "1") (pinfunction "1_1") (pintype "passive"))
      (node (ref "U1") (pin "14") (pinfunction "P14-PA3-EM4WU_14") (pintype "bidirectional"))
    )
    (net (code "7") (name "HEATER_PWM") (class "Default")
      (node (ref "R5") (pin "1") (pinfunction "1_1") (pintype "passive"))
      (node (ref "R6") (pin "2") (pinfunction "2_2") (pintype "passive"))
      (node (ref "U1") (pin "9") (pinfunction "P9-PD10(5V)_9") (pintype "bidirectional"))
    )
    (net (code "8") (name "I2C_CLK") (class "Default")
      (node (ref "J4") (pin "4") (pinfunction "4_4") (pintype "passive"))
      (node (ref "R16") (pin "1") (pinfunction "1_1") (pintype "passive"))
      (node (ref "U1") (pin "15") (pinfunction "P15-PA4_15") (pintype "bidirectional"))
    )
    (net (code "9") (name "I2C_DATA") (class "Default")
      (node (ref "J4") (pin "3") (pinfunction "3_3") (pintype "passive"))
      (node (ref "R17") (pin "1") (pinfunction "1_1") (pintype "passive"))
      (node (ref "U1") (pin "16") (pinfunction "P16-PA5(5V)_16") (pintype "bidirectional"))
    )
    (net (code "10") (name "JTAG_SWCLK") (class "Default")
      (node (ref "J3") (pin "4") (pinfunction "4_4") (pintype "bidirectional"))
      (node (ref "TP2") (pin "1") (pinfunction "TP_1") (pintype "bidirectional"))
      (node (ref "U1") (pin "28") (pinfunction "(5V)TCK-PF0-P28_28") (pintype "bidirectional"))
    )
    (net (code "11") (name "JTAG_SWDIO") (class "Default")
      (node (ref "J3") (pin "2") (pinfunction "2_2") (pintype "bidirectional"))
      (node (ref "TP3") (pin "1") (pinfunction "TP_1") (pintype "bidirectional"))
      (node (ref "U1") (pin "29") (pinfunction "(5V)TMS-PF1-P29_29") (pintype "bidirectional"))
    )
    (net (code "12") (name "JTAG_SWO") (class "Default")
      (node (ref "J3") (pin "6") (pinfunction "6_6") (pintype "bidirectional"))
      (node (ref "TP8") (pin "1") (pinfunction "TP_1") (pintype "bidirectional"))
      (node (ref "U1") (pin "26") (pinfunction "(5V)I2C1-PC11-P26_26") (pintype "bidirectional"))
    )
    (net (code "13") (name "Net-(C10-Pad1)") (class "Default")
      (node (ref "C10") (pin "1") (pinfunction "1_1") (pintype "passive"))
      (node (ref "D2") (pin "A") (pinfunction "A_A") (pintype "passive"))
      (node (ref "FB1") (pin "2") (pinfunction "2_2") (pintype "passive"))
      (node (ref "Q4") (pin "D") (pinfunction "D_D") (pintype "passive"))
    )
    (net (code "14") (name "Net-(D3-11)") (class "Default")
      (node (ref "D3") (pin "1") (pinfunction "11_1") (pintype "passive"))
      (node (ref "J2") (pin "1_1") (pinfunction "1_1_1_1") (pintype "passive"))
      (node (ref "J2") (pin "1_2") (pinfunction "1_2_1_2") (pintype "passive"))
      (node (ref "Q2") (pin "D") (pinfunction "D_D") (pintype "passive"))
    )
    (net (code "15") (name "Net-(J2-Pad3_1)") (class "Default")
      (node (ref "J2") (pin "3_1") (pinfunction "3_1_3_1") (pintype "passive"))
      (node (ref "J2") (pin "3_2") (pinfunction "3_2_3_2") (pintype "passive"))
      (node (ref "Q3") (pin "D") (pinfunction "D_D") (pintype "passive"))
    )
    (net (code "16") (name "Net-(Q1-D)") (class "Default")
      (node (ref "J1") (pin "5_1") (pinfunction "5_1_5_1") (pintype "passive"))
      (node (ref "J1") (pin "5_2") (pinfunction "5_2_5_2") (pintype "passive"))
      (node (ref "Q1") (pin "3") (pinfunction "D_3") (pintype "passive"))
      (node (ref "R1") (pin "1") (pinfunction "1_1") (pintype "passive"))
    )
    (net (code "17") (name "Net-(Q1-G)") (class "Default")
      (node (ref "Q1") (pin "1") (pinfunction "G_1") (pintype "passive"))
      (node (ref "R3") (pin "1") (pinfunction "1_1") (pintype "passive"))
    )
    (net (code "18") (name "Net-(Q2-PadG)") (class "Default")
      (node (ref "Q2") (pin "G") (pinfunction "G_G") (pintype "passive"))
      (node (ref "Q5") (pin "C") (pinfunction "C_C") (pintype "passive"))
      (node (ref "R2") (pin "1") (pinfunction "1_1") (pintype "passive"))
    )
    (net (code "19") (name "Net-(Q3-PadG)") (class "Default")
      (node (ref "Q3") (pin "G") (pinfunction "G_G") (pintype "passive"))
      (node (ref "R5") (pin "2") (pinfunction "2_2") (pintype "passive"))
    )
    (net (code "20") (name "Net-(Q4-PadG)") (class "Default")
      (node (ref "Q4") (pin "G") (pinfunction "G_G") (pintype "passive"))
      (node (ref "R14") (pin "2") (pinfunction "2_2") (pintype "passive"))
    )
    (net (code "21") (name "Net-(Q5-PadB)") (class "Default")
      (node (ref "Q5") (pin "B") (pinfunction "B_B") (pintype "passive"))
      (node (ref "R26") (pin "1") (pinfunction "1_1") (pintype "passive"))
    )
    (net (code "22") (name "Net-(R18-Pad2)") (class "Default")
      (node (ref "R18") (pin "2") (pinfunction "2_2") (pintype "passive"))
      (node (ref "V1") (pin "Y-A") (pinfunction "Y-A_Y-A") (pintype "passive"))
    )
    (net (code "23") (name "Net-(R19-Pad2)") (class "Default")
      (node (ref "R19") (pin "2") (pinfunction "2_2") (pintype "passive"))
      (node (ref "V1") (pin "G-A") (pinfunction "G-A_G-A") (pintype "passive"))
    )
    (net (code "24") (name "Net-(R20-Pad2)") (class "Default")
      (node (ref "R20") (pin "2") (pinfunction "2_2") (pintype "passive"))
      (node (ref "V2") (pin "G-A") (pinfunction "G-A_G-A") (pintype "passive"))
    )
    (net (code "25") (name "Net-(R21-Pad2)") (class "Default")
      (node (ref "R21") (pin "2") (pinfunction "2_2") (pintype "passive"))
      (node (ref "V2") (pin "Y-A") (pinfunction "Y-A_Y-A") (pintype "passive"))
    )
    (net (code "26") (name "Net-(U2-SW)") (class "Default")
      (node (ref "L1") (pin "1") (pinfunction "1_1") (pintype "passive"))
      (node (ref "U2") (pin "7") (pinfunction "SW_7") (pintype "bidirectional"))
    )
    (net (code "27") (name "POWER_GOOD") (class "Default")
      (node (ref "R11") (pin "1") (pinfunction "1_1") (pintype "passive"))
      (node (ref "U2") (pin "8") (pinfunction "PG_8") (pintype "bidirectional"))
    )
    (net (code "28") (name "SERIAL_RX") (class "Default")
      (node (ref "TP10") (pin "1") (pinfunction "TP_1") (pintype "bidirectional"))
      (node (ref "U1") (pin "23") (pinfunction "PB11-P23_23") (pintype "bidirectional"))
    )
    (net (code "29") (name "SERIAL_TX") (class "Default")
      (node (ref "TP11") (pin "1") (pinfunction "TP_1") (pintype "bidirectional"))
      (node (ref "U1") (pin "22") (pinfunction "PB12-P22_22") (pintype "bidirectional"))
    )
    (net (code "30") (name "VCC_+3.3V") (class "Default")
      (node (ref "C1") (pin "1") (pinfunction "1_1") (pintype "passive"))
      (node (ref "C3") (pin "1") (pinfunction "1_1") (pintype "passive"))
      (node (ref "C6") (pin "1") (pinfunction "1_1") (pintype "passive"))
      (node (ref "J4") (pin "1") (pinfunction "1_1") (pintype "passive"))
      (node (ref "L1") (pin "2") (pinfunction "2_2") (pintype "passive"))
      (node (ref "R10") (pin "2") (pinfunction "2_2") (pintype "passive"))
      (node (ref "R11") (pin "2") (pinfunction "2_2") (pintype "passive"))
      (node (ref "R12") (pin "2") (pinfunction "2_2") (pintype "passive"))
      (node (ref "R13") (pin "2") (pinfunction "2_2") (pintype "passive"))
      (node (ref "R15") (pin "2") (pinfunction "2_2") (pintype "passive"))
      (node (ref "R16") (pin "2") (pinfunction "2_2") (pintype "passive"))
      (node (ref "R17") (pin "2") (pinfunction "2_2") (pintype "passive"))
      (node (ref "R18") (pin "1") (pinfunction "1_1") (pintype "passive"))
      (node (ref "R19") (pin "1") (pinfunction "1_1") (pintype "passive"))
      (node (ref "R20") (pin "1") (pinfunction "1_1") (pintype "passive"))
      (node (ref "R21") (pin "1") (pinfunction "1_1") (pintype "passive"))
      (node (ref "R7") (pin "2") (pinfunction "2_2") (pintype "passive"))
      (node (ref "U1") (pin "17") (pinfunction "P17-VDDRAW(IN)_17") (pintype "bidirectional"))
      (node (ref "U2") (pin "6") (pinfunction "VOS_6") (pintype "bidirectional"))
    )
    (net (code "31") (name "VDD") (class "Default")
      (node (ref "C11") (pin "1") (pinfunction "1_1") (pintype "passive"))
      (node (ref "C5") (pin "1") (pinfunction "1_1") (pintype "passive"))
      (node (ref "D2") (pin "K") (pinfunction "K_K") (pintype "passive"))
      (node (ref "J2") (pin "2_1") (pinfunction "2_1_2_1") (pintype "passive"))
      (node (ref "J2") (pin "2_2") (pinfunction "2_2_2_2") (pintype "passive"))
      (node (ref "Q2") (pin "S") (pinfunction "S_S") (pintype "passive"))
      (node (ref "Q4") (pin "S") (pinfunction "S_S") (pintype "passive"))
      (node (ref "R1") (pin "2") (pinfunction "2_2") (pintype "passive"))
      (node (ref "R2") (pin "2") (pinfunction "2_2") (pintype "passive"))
      (node (ref "R24") (pin "2") (pinfunction "2_2") (pintype "passive"))
      (node (ref "TP7") (pin "1") (pinfunction "TP_1") (pintype "bidirectional"))
      (node (ref "U2") (pin "2") (pinfunction "VIN_2") (pintype "input"))
      (node (ref "U2") (pin "3") (pinfunction "EN_3") (pintype "bidirectional"))
    )
    (net (code "32") (name "VDDMAIN") (class "Default")
      (node (ref "C4") (pin "1") (pinfunction "1_1") (pintype "passive"))
      (node (ref "J3") (pin "1") (pinfunction "1_1") (pintype "bidirectional"))
      (node (ref "R22") (pin "2") (pinfunction "2_2") (pintype "passive"))
      (node (ref "TP4") (pin "1") (pinfunction "TP_1") (pintype "bidirectional"))
      (node (ref "U1") (pin "20") (pinfunction "(OUT)VDDMAIN-P20_20") (pintype "bidirectional"))
    )
    (net (code "33") (name "VDDRAW") (class "Default")
      (node (ref "C9") (pin "1") (pinfunction "1_1") (pintype "passive"))
      (node (ref "D1") (pin "1") (pinfunction "11_1") (pintype "passive"))
      (node (ref "FB1") (pin "1") (pinfunction "1_1") (pintype "passive"))
      (node (ref "J2") (pin "4_1") (pinfunction "4_1_4_1") (pintype "passive"))
      (node (ref "J2") (pin "4_2") (pinfunction "4_2_4_2") (pintype "passive"))
      (node (ref "TP6") (pin "1") (pinfunction "TP_1") (pintype "bidirectional"))
    )
    (net (code "34") (name "unconnected-(J3-Pad7)") (class "Default")
      (node (ref "J3") (pin "7") (pinfunction "7_7") (pintype "bidirectional"))
    )
    (net (code "35") (name "unconnected-(J3-Pad8)") (class "Default")
      (node (ref "J3") (pin "8") (pinfunction "8_8") (pintype "bidirectional"))
    )
    (net (code "36") (name "unconnected-(J3-Pad9)") (class "Default")
      (node (ref "J3") (pin "9") (pinfunction "9_9") (pintype "bidirectional"))
    )
    (net (code "37") (name "unconnected-(U1-(5V)PC6-P24-Pad24)") (class "Default")
      (node (ref "U1") (pin "24") (pinfunction "(5V)PC6-P24_24") (pintype "bidirectional"))
    )
    (net (code "38") (name "unconnected-(U1-RSVD-P33-Pad33)") (class "Default")
      (node (ref "U1") (pin "33") (pinfunction "RSVD-P33_33") (pintype "bidirectional"))
    )
    (net (code "39") (name "~{FAN_ENABLE}") (class "Default")
      (node (ref "R26") (pin "2") (pinfunction "2_2") (pintype "passive"))
      (node (ref "R4") (pin "2") (pinfunction "2_2") (pintype "passive"))
      (node (ref "U1") (pin "11") (pinfunction "P11-PA0_11") (pintype "bidirectional"))
    )
    (net (code "40") (name "~{FAN_PWM}") (class "Default")
      (node (ref "R25") (pin "1") (pinfunction "1_1") (pintype "passive"))
      (node (ref "R3") (pin "2") (pinfunction "2_2") (pintype "passive"))
      (node (ref "U1") (pin "12") (pinfunction "P12-PA1_12") (pintype "bidirectional"))
    )
    (net (code "41") (name "~{MODE_LED_GREEN}") (class "Default")
      (node (ref "U1") (pin "31") (pinfunction "(5V)TDI-PF3-P31_31") (pintype "bidirectional"))
      (node (ref "V1") (pin "G-K") (pinfunction "G-K_G-K") (pintype "passive"))
    )
    (net (code "42") (name "~{MODE_LED_YELLOW}") (class "Default")
      (node (ref "U1") (pin "30") (pinfunction "(5V)EM4WU-TDO-PF2-P30_30") (pintype "bidirectional"))
      (node (ref "V1") (pin "Y-K") (pinfunction "Y-K_Y-K") (pintype "passive"))
    )
    (net (code "43") (name "~{PUSH_BUTTON_MODE}") (class "Default")
      (node (ref "C8") (pin "1") (pinfunction "1_1") (pintype "passive"))
      (node (ref "R13") (pin "1") (pinfunction "1_1") (pintype "passive"))
      (node (ref "SW2") (pin "3") (pinfunction "3_3") (pintype "bidirectional"))
      (node (ref "SW2") (pin "4") (pinfunction "4_4") (pintype "bidirectional"))
      (node (ref "U1") (pin "25") (pinfunction "(5V)EM4WU-I2C1-PC10-P25_25") (pintype "bidirectional"))
    )
    (net (code "44") (name "~{PUSH_BUTTON_RESET}") (class "Default")
      (node (ref "C7") (pin "1") (pinfunction "1_1") (pintype "passive"))
      (node (ref "R12") (pin "1") (pinfunction "1_1") (pintype "passive"))
      (node (ref "SW1") (pin "3") (pinfunction "3_3") (pintype "bidirectional"))
      (node (ref "SW1") (pin "4") (pinfunction "4_4") (pintype "bidirectional"))
      (node (ref "U1") (pin "21") (pinfunction "EM4WU-PB13-P21_21") (pintype "bidirectional"))
    )
    (net (code "45") (name "~{RESET}") (class "Default")
      (node (ref "J3") (pin "10") (pinfunction "10_10") (pintype "bidirectional"))
      (node (ref "TP1") (pin "1") (pinfunction "TP_1") (pintype "bidirectional"))
      (node (ref "U1") (pin "32") (pinfunction "RSTN-P32_32") (pintype "bidirectional"))
    )
    (net (code "46") (name "~{SYS_LED_GREEN}") (class "Default")
      (node (ref "U1") (pin "8") (pinfunction "P8-PD11(5V)_8") (pintype "bidirectional"))
      (node (ref "V2") (pin "G-K") (pinfunction "G-K_G-K") (pintype "passive"))
    )
    (net (code "47") (name "~{SYS_LED_YELLOW}") (class "Default")
      (node (ref "U1") (pin "7") (pinfunction "P7-PD12(5V)_7") (pintype "bidirectional"))
      (node (ref "V2") (pin "Y-K") (pinfunction "Y-K_Y-K") (pintype "passive"))
    )
  )
)
